# Sheet2.net
KiCad netlist of a schematic drawn in Altium Designer
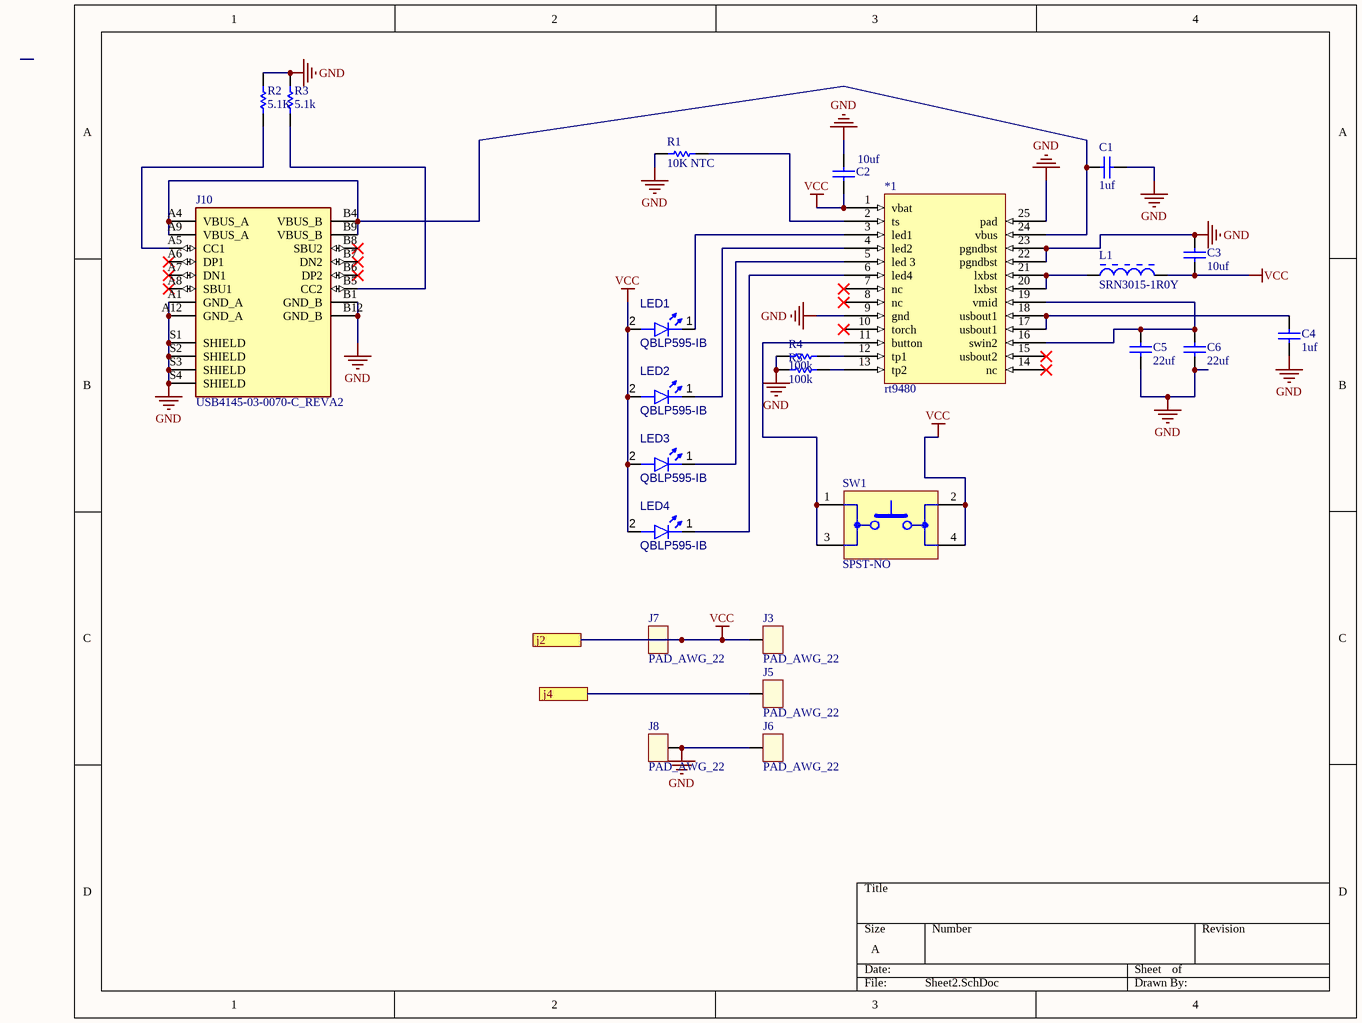
[diagram p0: Sheet2.SchDoc]

(export (version "E")
  (design (tool "Eeschema 10.0.6"))
  (components
    (comp (ref "*1")
      (value "rt9480")
      (footprint "QFN50P400X400X80_HS-25N")
      (description "power supply lipo")
      (libsource (lib "Ireti") (part "New symbol 1"))
    )
    (comp (ref "C1")
      (value "1uf")
      (footprint "C0201")
      (description "Capacitor")
      (libsource (lib "Simulation Generic Components") (part "Capacitor"))
    )
    (comp (ref "C2")
      (value "10uf")
      (footprint "C0201")
      (description "Capacitor")
      (libsource (lib "Simulation Generic Components") (part "Capacitor"))
    )
    (comp (ref "C3")
      (value "10uf")
      (footprint "C0201")
      (description "Capacitor")
      (libsource (lib "Simulation Generic Components") (part "Capacitor"))
    )
    (comp (ref "C4")
      (value "1uf")
      (footprint "C0201")
      (description "Capacitor")
      (libsource (lib "Simulation Generic Components") (part "Capacitor"))
    )
    (comp (ref "C5")
      (value "22uf")
      (footprint "C0201")
      (description "Capacitor")
      (libsource (lib "Simulation Generic Components") (part "Capacitor"))
    )
    (comp (ref "C6")
      (value "22uf")
      (footprint "C0201")
      (description "Capacitor")
      (libsource (lib "Simulation Generic Components") (part "Capacitor"))
    )
    (comp (ref "J3")
      (value "PAD_AWG_22")
      (footprint "PAD_0.4X0.6")
      (description "Pad for solder awg 22 wire")
      (libsource (lib "") (part "TP_25MILC_1_1"))
    )
    (comp (ref "J5")
      (value "PAD_AWG_22")
      (footprint "PAD_0.4X0.6")
      (description "Pad for solder awg 22 wire")
      (libsource (lib "") (part "TP_25MILC_1_1"))
    )
    (comp (ref "J6")
      (value "PAD_AWG_22")
      (footprint "PAD_0.4X0.6")
      (description "Pad for solder awg 22 wire")
      (libsource (lib "") (part "TP_25MILC_1_1"))
    )
    (comp (ref "J7")
      (value "PAD_AWG_22")
      (footprint "PAD_0.4X0.6")
      (description "Pad for solder awg 22 wire")
      (libsource (lib "Schlib_RHYNOKEY") (part "TP_25MILC_1"))
    )
    (comp (ref "J8")
      (value "PAD_AWG_22")
      (footprint "PAD_0.4X0.6")
      (description "Pad for solder awg 22 wire")
      (libsource (lib "Schlib_RHYNOKEY") (part "TP_25MILC_1"))
    )
    (comp (ref "J10")
      (value "USB4145-03-0070-C_REVA2")
      (footprint "GCT_USB4145-03-0070-C_REVA2")
      (description "Type C USB 2.0 Connector")
      (fields (field (name "MP") "USB4145-03-0070-C") (field (name "MF") "Global Connector Technology"))
      (libsource (lib "Ireti") (part "USB4145-03-0070-C_REVA2"))
    )
    (comp (ref "L1")
      (value "SRN3015-1R0Y")
      (footprint "BOUR-SRN3015-2_V")
      (fields (field (name "MANUFACTURER") "Bourns"))
      (libsource (lib "Altium Content Vault") (part "BOUR-IND-2A"))
    )
    (comp (ref "LED1")
      (value "QBLP595-IB")
      (footprint "QTB-QBLP595_V")
      (description "Chip LED 0402, Blue, 0.02 A, 3.1 to 3.7 V, -40 to 80 degC, 2-Pin SMD, RoHS, Tape and Reel")
      (libsource (lib "Ireti") (part "LED-KA-2"))
    )
    (comp (ref "LED2")
      (value "QBLP595-IB")
      (footprint "QTB-QBLP595_V")
      (description "Chip LED 0402, Blue, 0.02 A, 3.1 to 3.7 V, -40 to 80 degC, 2-Pin SMD, RoHS, Tape and Reel")
      (libsource (lib "Ireti") (part "LED-KA-2"))
    )
    (comp (ref "LED3")
      (value "QBLP595-IB")
      (footprint "QTB-QBLP595_V")
      (description "Chip LED 0402, Blue, 0.02 A, 3.1 to 3.7 V, -40 to 80 degC, 2-Pin SMD, RoHS, Tape and Reel")
      (libsource (lib "Ireti") (part "LED-KA-2"))
    )
    (comp (ref "LED4")
      (value "QBLP595-IB")
      (footprint "QTB-QBLP595_V")
      (description "Chip LED 0402, Blue, 0.02 A, 3.1 to 3.7 V, -40 to 80 degC, 2-Pin SMD, RoHS, Tape and Reel")
      (libsource (lib "Ireti") (part "LED-KA-2"))
    )
    (comp (ref "R1")
      (value "10K NTC")
      (footprint "RESC1005X40X25LL05T10")
      (fields (field (name "MANUFACTURER") "Yageo") (field (name "PART NUMBER") "RC0402FR-0725K5L"))
      (libsource (lib "Altium Content Vault") (part "RES"))
    )
    (comp (ref "R2")
      (value "5.1K")
      (footprint "R0201")
      (description "Resistor")
      (libsource (lib "Simulation Generic Components") (part "Resistor"))
    )
    (comp (ref "R3")
      (value "5.1k")
      (footprint "R0201")
      (description "Resistor")
      (libsource (lib "Simulation Generic Components") (part "Resistor"))
    )
    (comp (ref "R4")
      (value "100k")
      (footprint "R0201")
      (description "Resistor")
      (libsource (lib "Simulation Generic Components") (part "Resistor"))
    )
    (comp (ref "R5")
      (value "100k")
      (footprint "R0201")
      (description "Resistor")
      (libsource (lib "Simulation Generic Components") (part "Resistor"))
    )
    (comp (ref "SW1")
      (value "SPST-NO")
      (footprint "EVPAA802Q")
      (description "SWITCH TACTILE SPST-NO 0.02A 15V")
      (fields (field (name "MANUFACTURER") "Panasonic") (field (name "MANUFACTURER PART NUMBER") "EVPAA802Q"))
      (libsource (lib "Schlib_RHYNOKEY") (part "EVPAA802Q"))
    )
  )
  (nets
    (net (code "1") (name "/j4") (class "Default")
      (node (ref "J5") (pin "1") (pinfunction "1_1") (pintype "passive"))
    )
    (net (code "2") (name "GND") (class "Default")
      (node (ref "*1") (pin "22") (pinfunction "pgndbst_22") (pintype "input"))
      (node (ref "*1") (pin "23") (pinfunction "pgndbst_23") (pintype "input"))
      (node (ref "*1") (pin "25") (pinfunction "pad_25") (pintype "input"))
      (node (ref "*1") (pin "9") (pinfunction "gnd_9") (pintype "input"))
      (node (ref "C1") (pin "2") (pinfunction "2_2") (pintype "passive"))
      (node (ref "C2") (pin "2") (pinfunction "2_2") (pintype "passive"))
      (node (ref "C3") (pin "2") (pinfunction "2_2") (pintype "passive"))
      (node (ref "C4") (pin "1") (pinfunction "1_1") (pintype "passive"))
      (node (ref "C5") (pin "1") (pinfunction "1_1") (pintype "passive"))
      (node (ref "C6") (pin "1") (pinfunction "1_1") (pintype "passive"))
      (node (ref "J10") (pin "A1") (pinfunction "GND_A_A1") (pintype "power_in"))
      (node (ref "J10") (pin "A12") (pinfunction "GND_A_A12") (pintype "power_in"))
      (node (ref "J10") (pin "B1") (pinfunction "GND_B_B1") (pintype "power_in"))
      (node (ref "J10") (pin "B12") (pinfunction "GND_B_B12") (pintype "power_in"))
      (node (ref "J10") (pin "S1") (pinfunction "SHIELD_S1") (pintype "passive"))
      (node (ref "J10") (pin "S2") (pinfunction "SHIELD_S2") (pintype "passive"))
      (node (ref "J10") (pin "S3") (pinfunction "SHIELD_S3") (pintype "passive"))
      (node (ref "J10") (pin "S4") (pinfunction "SHIELD_S4") (pintype "passive"))
      (node (ref "J6") (pin "1") (pinfunction "1_1") (pintype "passive"))
      (node (ref "J8") (pin "1") (pinfunction "1_1") (pintype "passive"))
      (node (ref "R1") (pin "2") (pinfunction "2_2") (pintype "passive"))
      (node (ref "R2") (pin "2") (pinfunction "2_2") (pintype "passive"))
      (node (ref "R3") (pin "2") (pinfunction "2_2") (pintype "passive"))
      (node (ref "R4") (pin "1") (pinfunction "1_1") (pintype "passive"))
      (node (ref "R5") (pin "1") (pinfunction "1_1") (pintype "passive"))
    )
    (net (code "3") (name "Net-(*1-button)") (class "Default")
      (node (ref "*1") (pin "11") (pinfunction "button_11") (pintype "input"))
      (node (ref "SW1") (pin "1") (pinfunction "1_1") (pintype "passive"))
      (node (ref "SW1") (pin "3") (pinfunction "3_3") (pintype "passive"))
    )
    (net (code "4") (name "Net-(*1-led1)") (class "Default")
      (node (ref "*1") (pin "3") (pinfunction "led1_3") (pintype "input"))
      (node (ref "LED1") (pin "1") (pinfunction "K_1") (pintype "passive"))
    )
    (net (code "5") (name "Net-(*1-led2)") (class "Default")
      (node (ref "*1") (pin "4") (pinfunction "led2_4") (pintype "input"))
      (node (ref "LED2") (pin "1") (pinfunction "K_1") (pintype "passive"))
    )
    (net (code "6") (name "Net-(*1-led4)") (class "Default")
      (node (ref "*1") (pin "6") (pinfunction "led4_6") (pintype "input"))
      (node (ref "LED4") (pin "1") (pinfunction "K_1") (pintype "passive"))
    )
    (net (code "7") (name "Net-(*1-led_3)") (class "Default")
      (node (ref "*1") (pin "5") (pinfunction "led_3_5") (pintype "input"))
      (node (ref "LED3") (pin "1") (pinfunction "K_1") (pintype "passive"))
    )
    (net (code "8") (name "Net-(*1-lxbst-Pad20)") (class "Default")
      (node (ref "*1") (pin "20") (pinfunction "lxbst_20") (pintype "input"))
      (node (ref "*1") (pin "21") (pinfunction "lxbst_21") (pintype "input"))
      (node (ref "L1") (pin "1") (pinfunction "1_1") (pintype "passive"))
    )
    (net (code "9") (name "Net-(*1-swin2)") (class "Default")
      (node (ref "*1") (pin "16") (pinfunction "swin2_16") (pintype "input"))
      (node (ref "*1") (pin "19") (pinfunction "vmid_19") (pintype "input"))
      (node (ref "C5") (pin "2") (pinfunction "2_2") (pintype "passive"))
      (node (ref "C6") (pin "2") (pinfunction "2_2") (pintype "passive"))
    )
    (net (code "10") (name "Net-(*1-tp1)") (class "Default")
      (node (ref "*1") (pin "12") (pinfunction "tp1_12") (pintype "input"))
      (node (ref "R4") (pin "2") (pinfunction "2_2") (pintype "passive"))
    )
    (net (code "11") (name "Net-(*1-tp2)") (class "Default")
      (node (ref "*1") (pin "13") (pinfunction "tp2_13") (pintype "input"))
      (node (ref "R5") (pin "2") (pinfunction "2_2") (pintype "passive"))
    )
    (net (code "12") (name "Net-(*1-ts)") (class "Default")
      (node (ref "*1") (pin "2") (pinfunction "ts_2") (pintype "input"))
      (node (ref "R1") (pin "1") (pinfunction "1_1") (pintype "passive"))
    )
    (net (code "13") (name "Net-(*1-usbout1-Pad17)") (class "Default")
      (node (ref "*1") (pin "17") (pinfunction "usbout1_17") (pintype "input"))
      (node (ref "*1") (pin "18") (pinfunction "usbout1_18") (pintype "input"))
      (node (ref "C4") (pin "2") (pinfunction "2_2") (pintype "passive"))
    )
    (net (code "14") (name "Net-(*1-vbus)") (class "Default")
      (node (ref "*1") (pin "24") (pinfunction "vbus_24") (pintype "input"))
      (node (ref "C1") (pin "1") (pinfunction "1_1") (pintype "passive"))
      (node (ref "J10") (pin "A4") (pinfunction "VBUS_A_A4") (pintype "power_in"))
      (node (ref "J10") (pin "A9") (pinfunction "VBUS_A_A9") (pintype "power_in"))
      (node (ref "J10") (pin "B4") (pinfunction "VBUS_B_B4") (pintype "power_in"))
      (node (ref "J10") (pin "B9") (pinfunction "VBUS_B_B9") (pintype "power_in"))
    )
    (net (code "15") (name "Net-(J10-CC1)") (class "Default")
      (node (ref "J10") (pin "A5") (pinfunction "CC1_A5") (pintype "bidirectional"))
      (node (ref "R2") (pin "1") (pinfunction "1_1") (pintype "passive"))
    )
    (net (code "16") (name "Net-(J10-CC2)") (class "Default")
      (node (ref "J10") (pin "B5") (pinfunction "CC2_B5") (pintype "bidirectional"))
      (node (ref "R3") (pin "1") (pinfunction "1_1") (pintype "passive"))
    )
    (net (code "17") (name "VCC") (class "Default")
      (node (ref "*1") (pin "1") (pinfunction "vbat_1") (pintype "input"))
      (node (ref "C2") (pin "1") (pinfunction "1_1") (pintype "passive"))
      (node (ref "C3") (pin "1") (pinfunction "1_1") (pintype "passive"))
      (node (ref "J3") (pin "1") (pinfunction "1_1") (pintype "passive"))
      (node (ref "J7") (pin "1") (pinfunction "1_1") (pintype "passive"))
      (node (ref "L1") (pin "2") (pinfunction "2_2") (pintype "passive"))
      (node (ref "LED1") (pin "2") (pinfunction "A_2") (pintype "passive"))
      (node (ref "LED2") (pin "2") (pinfunction "A_2") (pintype "passive"))
      (node (ref "LED3") (pin "2") (pinfunction "A_2") (pintype "passive"))
      (node (ref "LED4") (pin "2") (pinfunction "A_2") (pintype "passive"))
      (node (ref "SW1") (pin "2") (pinfunction "2_2") (pintype "passive"))
      (node (ref "SW1") (pin "4") (pinfunction "4_4") (pintype "passive"))
    )
    (net (code "18") (name "unconnected-(*1-nc-Pad7)") (class "Default")
      (node (ref "*1") (pin "7") (pinfunction "nc_7") (pintype "input+no_connect"))
    )
    (net (code "19") (name "unconnected-(*1-nc-Pad8)") (class "Default")
      (node (ref "*1") (pin "8") (pinfunction "nc_8") (pintype "input+no_connect"))
    )
    (net (code "20") (name "unconnected-(*1-nc-Pad14)") (class "Default")
      (node (ref "*1") (pin "14") (pinfunction "nc_14") (pintype "input+no_connect"))
    )
    (net (code "21") (name "unconnected-(*1-torch-Pad10)") (class "Default")
      (node (ref "*1") (pin "10") (pinfunction "torch_10") (pintype "input+no_connect"))
    )
    (net (code "22") (name "unconnected-(*1-usbout2-Pad15)") (class "Default")
      (node (ref "*1") (pin "15") (pinfunction "usbout2_15") (pintype "input+no_connect"))
    )
    (net (code "23") (name "unconnected-(J10-DN1-PadA7)") (class "Default")
      (node (ref "J10") (pin "A7") (pinfunction "DN1_A7") (pintype "bidirectional+no_connect"))
    )
    (net (code "24") (name "unconnected-(J10-DN2-PadB7)") (class "Default")
      (node (ref "J10") (pin "B7") (pinfunction "DN2_B7") (pintype "bidirectional+no_connect"))
    )
    (net (code "25") (name "unconnected-(J10-DP1-PadA6)") (class "Default")
      (node (ref "J10") (pin "A6") (pinfunction "DP1_A6") (pintype "bidirectional+no_connect"))
    )
    (net (code "26") (name "unconnected-(J10-DP2-PadB6)") (class "Default")
      (node (ref "J10") (pin "B6") (pinfunction "DP2_B6") (pintype "bidirectional+no_connect"))
    )
    (net (code "27") (name "unconnected-(J10-SBU1-PadA8)") (class "Default")
      (node (ref "J10") (pin "A8") (pinfunction "SBU1_A8") (pintype "bidirectional+no_connect"))
    )
    (net (code "28") (name "unconnected-(J10-SBU2-PadB8)") (class "Default")
      (node (ref "J10") (pin "B8") (pinfunction "SBU2_B8") (pintype "bidirectional+no_connect"))
    )
  )
)
